# microBoard_DRV8843.net
KiCad netlist of a schematic drawn in EAGLE
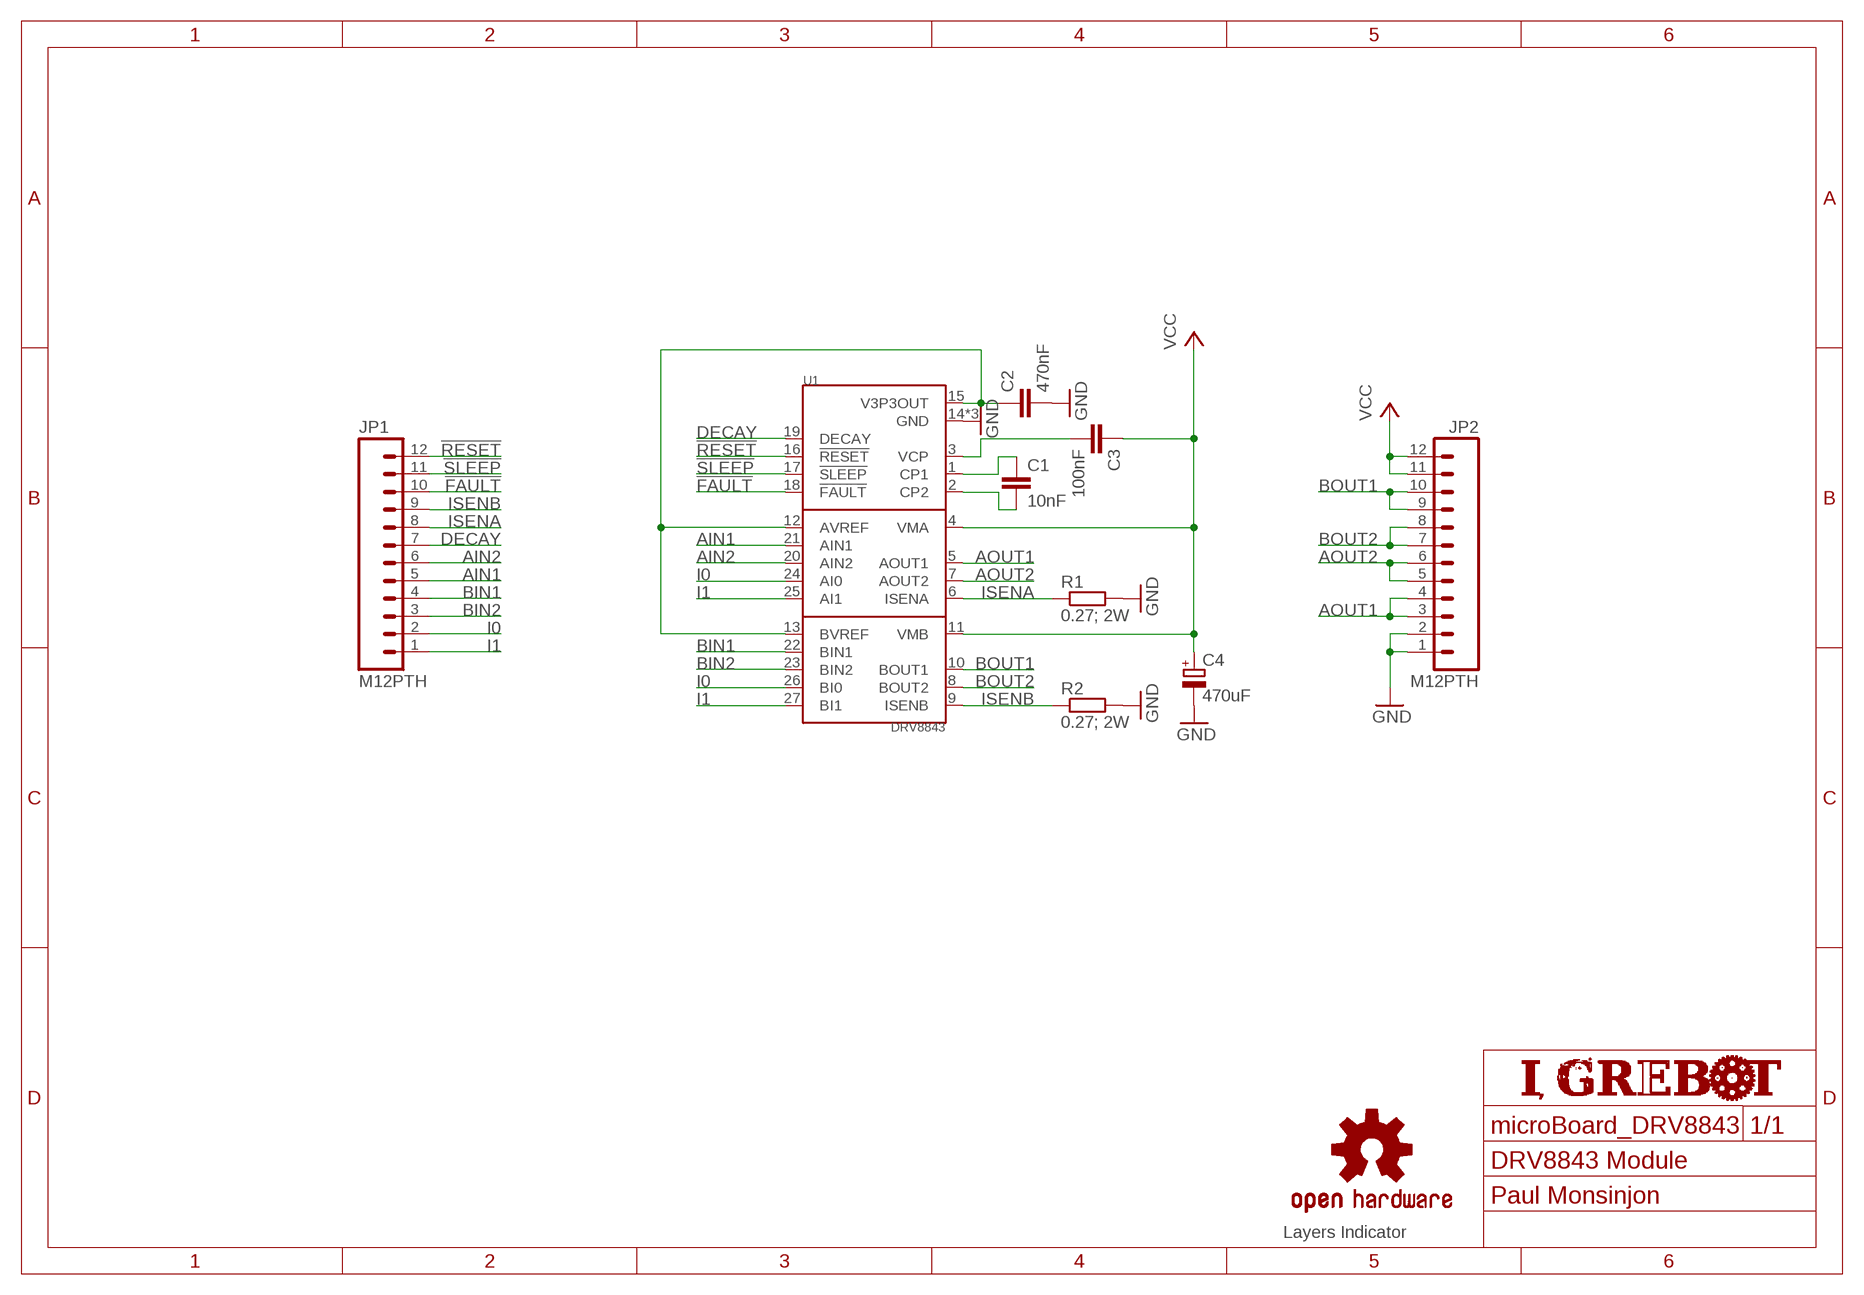
[diagram p0: schematic, sheet 1]

(export (version "E")
  (design (tool "Eeschema 10.0.6"))
  (components
    (comp (ref "C1")
      (value "10nF")
      (footprint "eagle-import:C0603")
      (libsource (lib "eagle-import") (part "C-EUC0603"))
    )
    (comp (ref "C2")
      (value "470nF")
      (footprint "eagle-import:C0603")
      (libsource (lib "eagle-import") (part "C-EUC0603"))
    )
    (comp (ref "C3")
      (value "100nF")
      (footprint "eagle-import:C0603")
      (libsource (lib "eagle-import") (part "C-EUC0603"))
    )
    (comp (ref "C4")
      (value "470uF")
      (footprint "eagle-import:PANASONIC_D")
      (libsource (lib "eagle-import") (part "CPOL-EUD"))
    )
    (comp (ref "JP1")
      (value "M12PTH")
      (footprint "eagle-import:1X12")
      (libsource (lib "eagle-import") (part "M12PTH"))
    )
    (comp (ref "JP2")
      (value "M12PTH")
      (footprint "eagle-import:1X12")
      (libsource (lib "eagle-import") (part "M12PTH"))
    )
    (comp (ref "LOGO1")
      (value "OSHW-LOGOS")
      (footprint "eagle-import:OSHW-LOGO-S")
      (libsource (lib "eagle-import") (part "OSHW-LOGOS"))
    )
    (comp (ref "R1")
      (value "0.27; 2W")
      (footprint "eagle-import:R2010")
      (libsource (lib "eagle-import") (part "R-EU_R2010"))
    )
    (comp (ref "R2")
      (value "0.27; 2W")
      (footprint "eagle-import:R2010")
      (libsource (lib "eagle-import") (part "R-EU_R2010"))
    )
    (comp (ref "U$1")
      (value "LOGO_IGREBOT12X2MM")
      (footprint "eagle-import:IGREBOT_12X2MM")
      (libsource (lib "eagle-import") (part "LOGO_IGREBOT12X2MM"))
    )
    (comp (ref "U$2")
      (value "LAYERS_CHECK4_LAYERS")
      (footprint "eagle-import:LAYERS_CHECK_4")
      (libsource (lib "eagle-import") (part "LAYERS_CHECK4_LAYERS"))
    )
    (comp (ref "U1")
      (value "DRV8843")
      (footprint "eagle-import:PWP_28")
      (libsource (lib "eagle-import") (part "DRV8843"))
    )
  )
  (nets
    (net (code "1") (name "/AIN1") (class "Default")
      (node (ref "JP1") (pin "5") (pinfunction "5_5") (pintype "passive"))
      (node (ref "U1") (pin "21") (pinfunction "AIN1_21") (pintype "bidirectional"))
    )
    (net (code "2") (name "/AIN2") (class "Default")
      (node (ref "JP1") (pin "6") (pinfunction "6_6") (pintype "passive"))
      (node (ref "U1") (pin "20") (pinfunction "AIN2_20") (pintype "bidirectional"))
    )
    (net (code "3") (name "/AOUT1") (class "Default")
      (node (ref "JP2") (pin "3") (pinfunction "3_3") (pintype "passive"))
      (node (ref "JP2") (pin "4") (pinfunction "4_4") (pintype "passive"))
      (node (ref "U1") (pin "5") (pinfunction "AOUT1_5") (pintype "bidirectional"))
    )
    (net (code "4") (name "/AOUT2") (class "Default")
      (node (ref "JP2") (pin "5") (pinfunction "5_5") (pintype "passive"))
      (node (ref "JP2") (pin "6") (pinfunction "6_6") (pintype "passive"))
      (node (ref "U1") (pin "7") (pinfunction "AOUT2_7") (pintype "bidirectional"))
    )
    (net (code "5") (name "/BIN1") (class "Default")
      (node (ref "JP1") (pin "4") (pinfunction "4_4") (pintype "passive"))
      (node (ref "U1") (pin "22") (pinfunction "BIN1_22") (pintype "bidirectional"))
    )
    (net (code "6") (name "/BIN2") (class "Default")
      (node (ref "JP1") (pin "3") (pinfunction "3_3") (pintype "passive"))
      (node (ref "U1") (pin "23") (pinfunction "BIN2_23") (pintype "bidirectional"))
    )
    (net (code "7") (name "/BOUT1") (class "Default")
      (node (ref "JP2") (pin "10") (pinfunction "10_10") (pintype "passive"))
      (node (ref "JP2") (pin "9") (pinfunction "9_9") (pintype "passive"))
      (node (ref "U1") (pin "10") (pinfunction "BOUT1_10") (pintype "bidirectional"))
    )
    (net (code "8") (name "/BOUT2") (class "Default")
      (node (ref "JP2") (pin "7") (pinfunction "7_7") (pintype "passive"))
      (node (ref "JP2") (pin "8") (pinfunction "8_8") (pintype "passive"))
      (node (ref "U1") (pin "8") (pinfunction "BOUT2_8") (pintype "bidirectional"))
    )
    (net (code "9") (name "/DECAY") (class "Default")
      (node (ref "JP1") (pin "7") (pinfunction "7_7") (pintype "passive"))
      (node (ref "U1") (pin "19") (pinfunction "DECAY_19") (pintype "bidirectional"))
    )
    (net (code "10") (name "/I0") (class "Default")
      (node (ref "JP1") (pin "2") (pinfunction "2_2") (pintype "passive"))
      (node (ref "U1") (pin "24") (pinfunction "AI0_24") (pintype "bidirectional"))
      (node (ref "U1") (pin "26") (pinfunction "BI0_26") (pintype "bidirectional"))
    )
    (net (code "11") (name "/I1") (class "Default")
      (node (ref "JP1") (pin "1") (pinfunction "1_1") (pintype "passive"))
      (node (ref "U1") (pin "25") (pinfunction "AI1_25") (pintype "bidirectional"))
      (node (ref "U1") (pin "27") (pinfunction "BI1_27") (pintype "bidirectional"))
    )
    (net (code "12") (name "/ISENA") (class "Default")
      (node (ref "JP1") (pin "8") (pinfunction "8_8") (pintype "passive"))
      (node (ref "R1") (pin "1") (pinfunction "1_1") (pintype "passive"))
      (node (ref "U1") (pin "6") (pinfunction "ISENA_6") (pintype "bidirectional"))
    )
    (net (code "13") (name "/ISENB") (class "Default")
      (node (ref "JP1") (pin "9") (pinfunction "9_9") (pintype "passive"))
      (node (ref "R2") (pin "1") (pinfunction "1_1") (pintype "passive"))
      (node (ref "U1") (pin "9") (pinfunction "ISENB_9") (pintype "bidirectional"))
    )
    (net (code "14") (name "/~{FAULT}") (class "Default")
      (node (ref "JP1") (pin "10") (pinfunction "10_10") (pintype "passive"))
      (node (ref "U1") (pin "18") (pinfunction "~{FAULT}_18") (pintype "bidirectional"))
    )
    (net (code "15") (name "/~{RESET}") (class "Default")
      (node (ref "JP1") (pin "12") (pinfunction "12_12") (pintype "passive"))
      (node (ref "U1") (pin "16") (pinfunction "~{RESET}_16") (pintype "bidirectional"))
    )
    (net (code "16") (name "/~{SLEEP}") (class "Default")
      (node (ref "JP1") (pin "11") (pinfunction "11_11") (pintype "passive"))
      (node (ref "U1") (pin "17") (pinfunction "~{SLEEP}_17") (pintype "bidirectional"))
    )
    (net (code "17") (name "GND") (class "Default")
      (node (ref "C2") (pin "2") (pinfunction "2_2") (pintype "passive"))
      (node (ref "C4") (pin "-") (pinfunction "-_-") (pintype "passive"))
      (node (ref "JP2") (pin "1") (pinfunction "1_1") (pintype "passive"))
      (node (ref "JP2") (pin "2") (pinfunction "2_2") (pintype "passive"))
      (node (ref "R1") (pin "2") (pinfunction "2_2") (pintype "passive"))
      (node (ref "R2") (pin "2") (pinfunction "2_2") (pintype "passive"))
      (node (ref "U1") (pin "14") (pinfunction "GND_14") (pintype "power_in"))
      (node (ref "U1") (pin "28") (pinfunction "GND_28") (pintype "power_in"))
      (node (ref "U1") (pin "PPAD") (pinfunction "GND_PPAD") (pintype "power_in"))
    )
    (net (code "18") (name "Net-(U1-AVREF)") (class "Default")
      (node (ref "C2") (pin "1") (pinfunction "1_1") (pintype "passive"))
      (node (ref "U1") (pin "12") (pinfunction "AVREF_12") (pintype "bidirectional"))
      (node (ref "U1") (pin "13") (pinfunction "BVREF_13") (pintype "bidirectional"))
      (node (ref "U1") (pin "15") (pinfunction "V3P3OUT_15") (pintype "power_in"))
    )
    (net (code "19") (name "Net-(U1-CP1)") (class "Default")
      (node (ref "C1") (pin "1") (pinfunction "1_1") (pintype "passive"))
      (node (ref "U1") (pin "1") (pinfunction "CP1_1") (pintype "bidirectional"))
    )
    (net (code "20") (name "Net-(U1-CP2)") (class "Default")
      (node (ref "C1") (pin "2") (pinfunction "2_2") (pintype "passive"))
      (node (ref "U1") (pin "2") (pinfunction "CP2_2") (pintype "bidirectional"))
    )
    (net (code "21") (name "Net-(U1-VCP)") (class "Default")
      (node (ref "C3") (pin "2") (pinfunction "2_2") (pintype "passive"))
      (node (ref "U1") (pin "3") (pinfunction "VCP_3") (pintype "passive"))
    )
    (net (code "22") (name "VCC") (class "Default")
      (node (ref "C3") (pin "1") (pinfunction "1_1") (pintype "passive"))
      (node (ref "C4") (pin "+") (pinfunction "+_+") (pintype "passive"))
      (node (ref "JP2") (pin "11") (pinfunction "11_11") (pintype "passive"))
      (node (ref "JP2") (pin "12") (pinfunction "12_12") (pintype "passive"))
      (node (ref "U1") (pin "11") (pinfunction "VMB_11") (pintype "power_in"))
      (node (ref "U1") (pin "4") (pinfunction "VMA_4") (pintype "power_in"))
    )
  )
)
